# Driver_Motor_Dir.net
KiCad netlist of a schematic drawn in Altium Designer
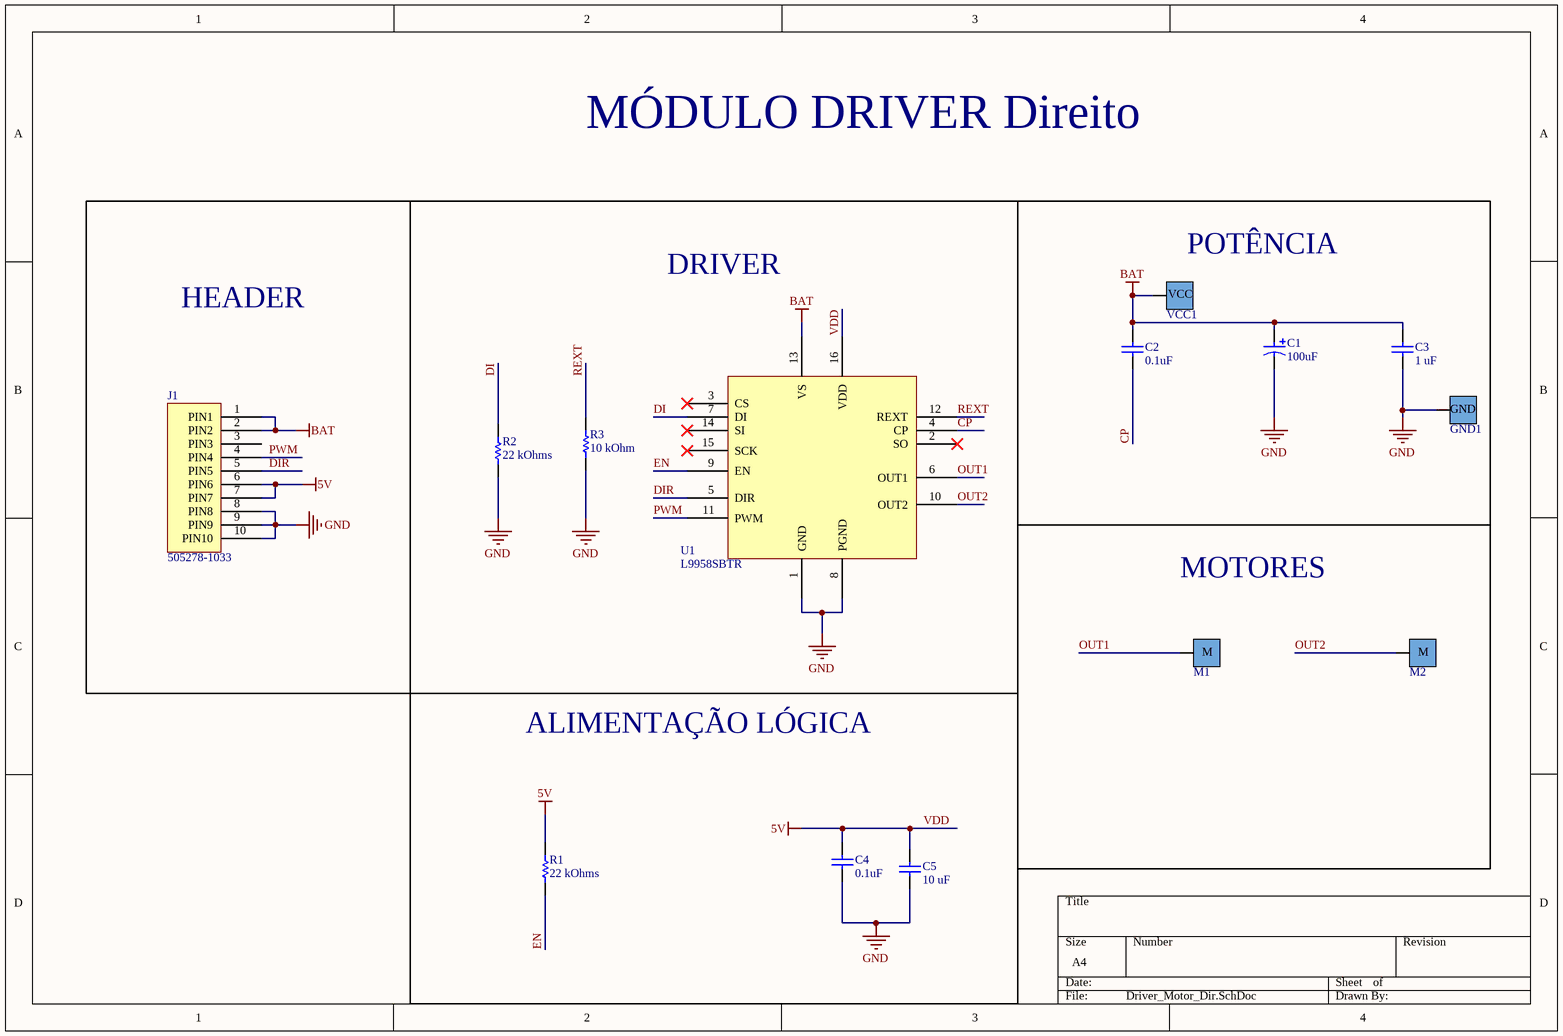
[diagram p0: Driver_Motor_Dir.SchDoc]

(export (version "E")
  (design (tool "Eeschema 10.0.6"))
  (components
    (comp (ref "C1")
      (value "100uF")
      (footprint "TANTALUM C0805")
      (description "CAP TAN 100uF 6.3V 0805")
      (fields
        (field (name "MANUFACTURER") "AVX")
        (field (name "PART NUMBER") "F980J107MSA")
        (field (name "LIBRARY CONTROL - PERSON THAT CHECKED FOOTPRINT") "Nikaum")
        (field (name "LIBRARY CONTROL - PERSON THAT CHECKED SCHEMATIC") "Nikaum")
        (field (name "LIBRARY CONTROL - PERSON THAT DID THE LAST UPDATE FOOTPRINT") "Nikaum")
        (field (name "LIBRARY CONTROL - PERSON THAT DID THE LAST UPDATE SCHEMATIC") "Nikaum")
      )
      (libsource (lib "Uai!Tecas") (part "F980J107MSA"))
    )
    (comp (ref "C2")
      (value "0.1uF")
      (footprint "C0805")
      (description "CAP CER 100nF 25V X7R 0805")
      (fields
        (field (name "MANUFACTURER") "Kemet")
        (field (name "PART NUMBER") "C0805C104M3RACTU")
        (field (name "LIBRARY CONTROL - PERSON THAT CHECKED FOOTPRINT") "Cage")
        (field (name "LIBRARY CONTROL - PERSON THAT CHECKED SCHEMATIC") "Cage")
        (field (name "LIBRARY CONTROL - PERSON THAT DID THE LAST UPDATE FOOTPRINT") "Cage")
        (field (name "LIBRARY CONTROL - PERSON THAT DID THE LAST UPDATE SCHEMATIC") "Cage")
      )
      (libsource (lib "Uai!Tecas") (part "C0805C104M3RACTU"))
    )
    (comp (ref "C3")
      (value "1 uF")
      (footprint "C0805")
      (description "CAP CER 1uF 100V X7R 0805")
      (fields (field (name "MANUFACTURER") "KYOCERA AVX") (field (name "PART NUMBER") "08051C105K4T2A"))
      (libsource (lib "Uai!Tecas") (part "08051C105K4T2A"))
    )
    (comp (ref "C4")
      (value "0.1uF")
      (footprint "C0805")
      (description "CAP CER 100nF 25V X7R 0805")
      (fields
        (field (name "MANUFACTURER") "Kemet")
        (field (name "PART NUMBER") "C0805C104M3RACTU")
        (field (name "LIBRARY CONTROL - PERSON THAT CHECKED FOOTPRINT") "Cage")
        (field (name "LIBRARY CONTROL - PERSON THAT CHECKED SCHEMATIC") "Cage")
        (field (name "LIBRARY CONTROL - PERSON THAT DID THE LAST UPDATE FOOTPRINT") "Cage")
        (field (name "LIBRARY CONTROL - PERSON THAT DID THE LAST UPDATE SCHEMATIC") "Cage")
      )
      (libsource (lib "Uai!Tecas") (part "C0805C104M3RACTU"))
    )
    (comp (ref "C5")
      (value "10 uF")
      (footprint "C0603")
      (description "CAP CER 10uF 25V X5R 0603")
      (fields
        (field (name "MANUFACTURER") "TDK")
        (field (name "PART NUMBER") "C1608X5R1E106M080AC")
        (field (name "LIBRARY CONTROL - PERSON THAT CHECKED FOOTPRINT") "Nikaum")
        (field (name "LIBRARY CONTROL - PERSON THAT CHECKED SCHEMATIC") "Nikaum")
        (field (name "LIBRARY CONTROL - PERSON THAT DID THE LAST UPDATE FOOTPRINT") "Nikaum")
        (field (name "LIBRARY CONTROL - PERSON THAT DID THE LAST UPDATE SCHEMATIC") "Nikaum")
      )
      (libsource (lib "Uai!Tecas") (part "C1608X5R1E106M080AC"))
    )
    (comp (ref "GND1")
      (value "Ground Pad")
      (footprint "PAD_ALIMENTAÇÃO_MINI")
      (description "GND PAD MINI SUMÔ")
      (libsource (lib "Uai!Tecas") (part "Ground Pad Mini Sumô"))
    )
    (comp (ref "J1")
      (value "505278-1033")
      (footprint "FPC_CON")
      (description "CONN FFC/FPC HORZ 10POS 0.50MM")
      (fields
        (field (name "MANUFACTURER") "Molex")
        (field (name "LIBRARY CONTROL - PERSON THAT CHECKED FOOTPRINT") "Lucas")
        (field (name "LIBRARY CONTROL - PERSON THAT CHECKED SCHEMATIC") "Lucas")
        (field (name "LIBRARY CONTROL - PERSON THAT DID THE LAST UPDATE FOOTPRINT") "Mateus(Dimas)")
        (field (name "LIBRARY CONTROL - PERSON THAT DID THE LAST UPDATE SCHEMATIC") "Mateus(Dimas)")
      )
      (libsource (lib "Uai!Tecas") (part "505278-1033_BODY"))
    )
    (comp (ref "M1")
      (value "Motor Pad")
      (footprint "PAD_MOTOR_MINI")
      (description "MOTOR PAD MINI SUMÔ")
      (libsource (lib "Uai!Tecas") (part "Motor Pad Mini Sumô"))
    )
    (comp (ref "M2")
      (value "Motor Pad")
      (footprint "PAD_MOTOR_MINI")
      (description "MOTOR PAD MINI SUMÔ")
      (libsource (lib "Uai!Tecas") (part "Motor Pad Mini Sumô"))
    )
    (comp (ref "R1")
      (value "22 kOhms")
      (footprint "RESISTOR_0603")
      (description "RES SMD 22K OHM 1% 1/5W 0603")
      (fields
        (field (name "MANUFACTURER") "TE Connectivity / Holsworthy")
        (field (name "PART NUMBER") "CRGH0603F22K")
      )
      (libsource (lib "Uai!Tecas") (part "CRGH0603F22K"))
    )
    (comp (ref "R2")
      (value "22 kOhms")
      (footprint "RESISTOR_0603")
      (description "RES SMD 22K OHM 1% 1/5W 0603")
      (fields
        (field (name "MANUFACTURER") "TE Connectivity / Holsworthy")
        (field (name "PART NUMBER") "CRGH0603F22K")
      )
      (libsource (lib "Uai!Tecas") (part "CRGH0603F22K"))
    )
    (comp (ref "R3")
      (value "10 kOhm")
      (footprint "RESISTOR_0603")
      (description "RES SMD 10 kOHM 1% 1/10W 0603")
      (fields (field (name "MANUFACTURER") "Vishay") (field (name "PART NUMBER") "CRCW060310K0FKEBC"))
      (libsource (lib "Uai!Tecas") (part "CRCW060310K0FKEBC"))
    )
    (comp (ref "U1")
      (value "L9958SBTR")
      (footprint "POWERSO16 (16_PINS)")
      (description "IC MTR DRV (4V ~ 28V) (100 uA) POWERSO 16")
      (fields
        (field (name "MANUFACTURER") "ST")
        (field (name "LIBRARY CONTROL - PERSON THAT CHECKED SCHEMATIC") "Pierre")
        (field (name "LIBRARY CONTROL - PERSON THAT CHECKED FOOTPRINT") "Pierre")
        (field (name "LIBRARY CONTROL - PERSON THAT DID THE LAST UPDATE SCHEMATIC") "Pierre")
        (field (name "LIBRARY CONTROL - PERSON THAT DID THE LAST UPDATE FOOTPRINT") "Stéfany(Ster)")
      )
      (libsource (lib "Uai!Tecas") (part "L9958SBTR"))
    )
    (comp (ref "VCC1")
      (value "Source Pad")
      (footprint "PAD_ALIMENTAÇÃO_MINI")
      (description "VCC PAD MINI SUMÔ")
      (libsource (lib "Uai!Tecas") (part "Source Pad Mini Sumô"))
    )
  )
  (nets
    (net (code "1") (name "/CP") (class "Default")
      (node (ref "C2") (pin "1") (pinfunction "1_1") (pintype "passive"))
      (node (ref "U1") (pin "4") (pinfunction "CP_4") (pintype "passive"))
    )
    (net (code "2") (name "/DI") (class "Default")
      (node (ref "R2") (pin "2") (pinfunction "2_2") (pintype "passive"))
      (node (ref "U1") (pin "7") (pinfunction "DI_7") (pintype "passive"))
    )
    (net (code "3") (name "/DIR") (class "Default")
      (node (ref "J1") (pin "5") (pinfunction "PIN5_5") (pintype "passive"))
      (node (ref "U1") (pin "5") (pinfunction "DIR_5") (pintype "passive"))
    )
    (net (code "4") (name "/EN") (class "Default")
      (node (ref "R1") (pin "2") (pinfunction "2_2") (pintype "passive"))
      (node (ref "U1") (pin "9") (pinfunction "EN_9") (pintype "passive"))
    )
    (net (code "5") (name "/OUT1") (class "Default")
      (node (ref "M1") (pin "M") (pinfunction "M_M") (pintype "passive"))
      (node (ref "U1") (pin "6") (pinfunction "OUT1_6") (pintype "passive"))
    )
    (net (code "6") (name "/OUT2") (class "Default")
      (node (ref "M2") (pin "M") (pinfunction "M_M") (pintype "passive"))
      (node (ref "U1") (pin "10") (pinfunction "OUT2_10") (pintype "passive"))
    )
    (net (code "7") (name "/PWM") (class "Default")
      (node (ref "J1") (pin "4") (pinfunction "PIN4_4") (pintype "passive"))
      (node (ref "U1") (pin "11") (pinfunction "PWM_11") (pintype "passive"))
    )
    (net (code "8") (name "/REXT") (class "Default")
      (node (ref "R3") (pin "2") (pinfunction "2_2") (pintype "passive"))
      (node (ref "U1") (pin "12") (pinfunction "REXT_12") (pintype "passive"))
    )
    (net (code "9") (name "5V") (class "Default")
      (node (ref "C4") (pin "2") (pinfunction "2_2") (pintype "passive"))
      (node (ref "C5") (pin "2") (pinfunction "2_2") (pintype "passive"))
      (node (ref "J1") (pin "6") (pinfunction "PIN6_6") (pintype "passive"))
      (node (ref "J1") (pin "7") (pinfunction "PIN7_7") (pintype "passive"))
      (node (ref "R1") (pin "1") (pinfunction "1_1") (pintype "passive"))
      (node (ref "U1") (pin "16") (pinfunction "VDD_16") (pintype "passive"))
    )
    (net (code "10") (name "BAT") (class "Default")
      (node (ref "C1") (pin "1") (pinfunction "1_1") (pintype "passive"))
      (node (ref "C2") (pin "2") (pinfunction "2_2") (pintype "passive"))
      (node (ref "C3") (pin "2") (pinfunction "2_2") (pintype "passive"))
      (node (ref "J1") (pin "1") (pinfunction "PIN1_1") (pintype "passive"))
      (node (ref "J1") (pin "2") (pinfunction "PIN2_2") (pintype "passive"))
      (node (ref "U1") (pin "13") (pinfunction "VS_13") (pintype "passive"))
      (node (ref "VCC1") (pin "A") (pinfunction "VCC_A") (pintype "passive"))
    )
    (net (code "11") (name "GND") (class "Default")
      (node (ref "C1") (pin "2") (pinfunction "2_2") (pintype "passive"))
      (node (ref "C3") (pin "1") (pinfunction "1_1") (pintype "passive"))
      (node (ref "C4") (pin "1") (pinfunction "1_1") (pintype "passive"))
      (node (ref "C5") (pin "1") (pinfunction "1_1") (pintype "passive"))
      (node (ref "GND1") (pin "A") (pinfunction "GND_A") (pintype "passive"))
      (node (ref "J1") (pin "10") (pinfunction "PIN10_10") (pintype "passive"))
      (node (ref "J1") (pin "8") (pinfunction "PIN8_8") (pintype "passive"))
      (node (ref "J1") (pin "9") (pinfunction "PIN9_9") (pintype "passive"))
      (node (ref "R2") (pin "1") (pinfunction "1_1") (pintype "passive"))
      (node (ref "R3") (pin "1") (pinfunction "1_1") (pintype "passive"))
      (node (ref "U1") (pin "1") (pinfunction "GND_1") (pintype "passive"))
      (node (ref "U1") (pin "8") (pinfunction "PGND_8") (pintype "passive"))
    )
    (net (code "12") (name "unconnected-(J1-PIN3-Pad3)") (class "Default")
      (node (ref "J1") (pin "3") (pinfunction "PIN3_3") (pintype "passive"))
    )
    (net (code "13") (name "unconnected-(U1-CS-Pad3)") (class "Default")
      (node (ref "U1") (pin "3") (pinfunction "CS_3") (pintype "passive+no_connect"))
    )
    (net (code "14") (name "unconnected-(U1-SCK-Pad15)") (class "Default")
      (node (ref "U1") (pin "15") (pinfunction "SCK_15") (pintype "passive+no_connect"))
    )
    (net (code "15") (name "unconnected-(U1-SI-Pad14)") (class "Default")
      (node (ref "U1") (pin "14") (pinfunction "SI_14") (pintype "passive+no_connect"))
    )
    (net (code "16") (name "unconnected-(U1-SO-Pad2)") (class "Default")
      (node (ref "U1") (pin "2") (pinfunction "SO_2") (pintype "passive+no_connect"))
    )
  )
)
